# Disco-Cart_2.net
KiCad netlist of a schematic drawn in EAGLE
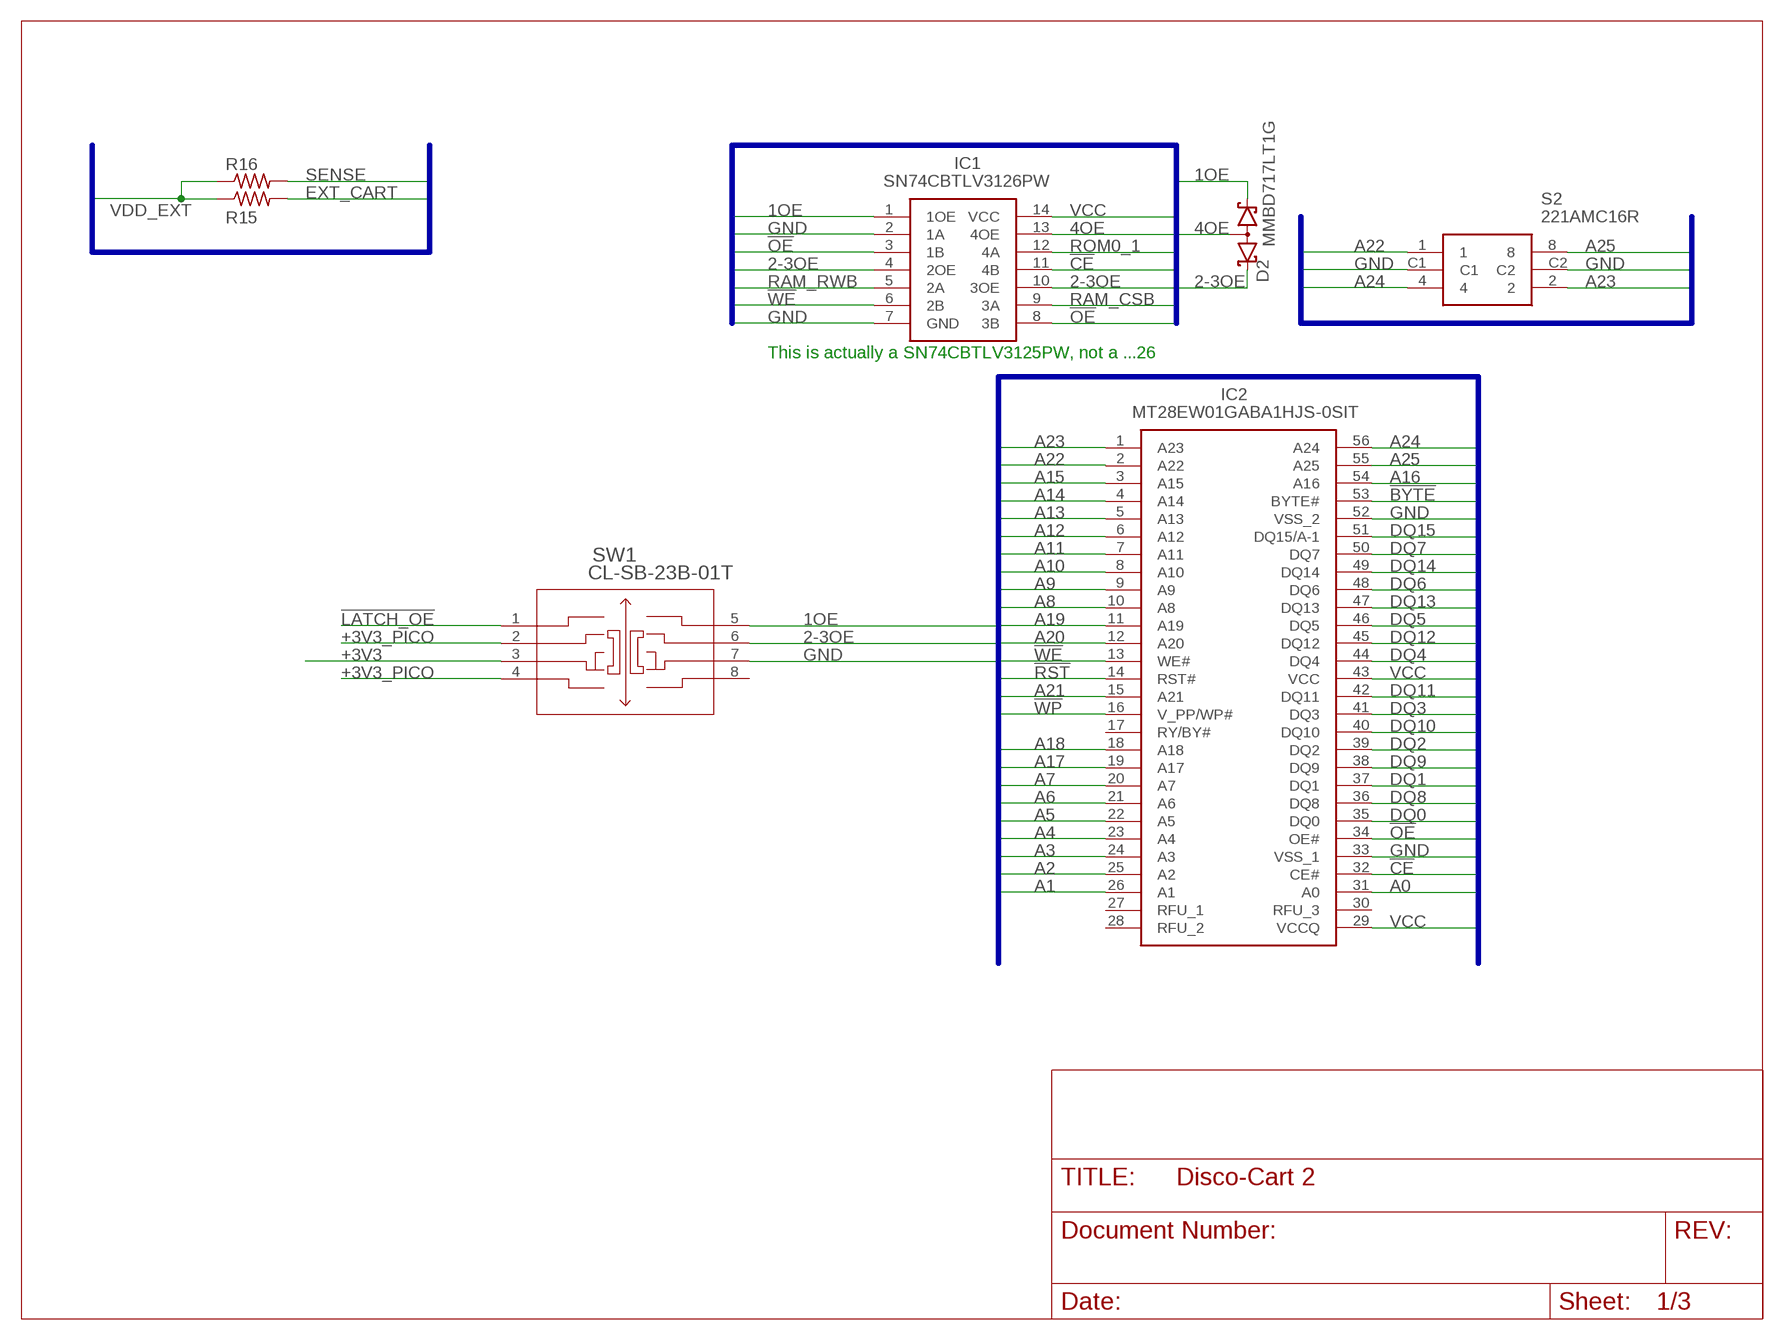
[diagram p0: schematic, sheet 1]
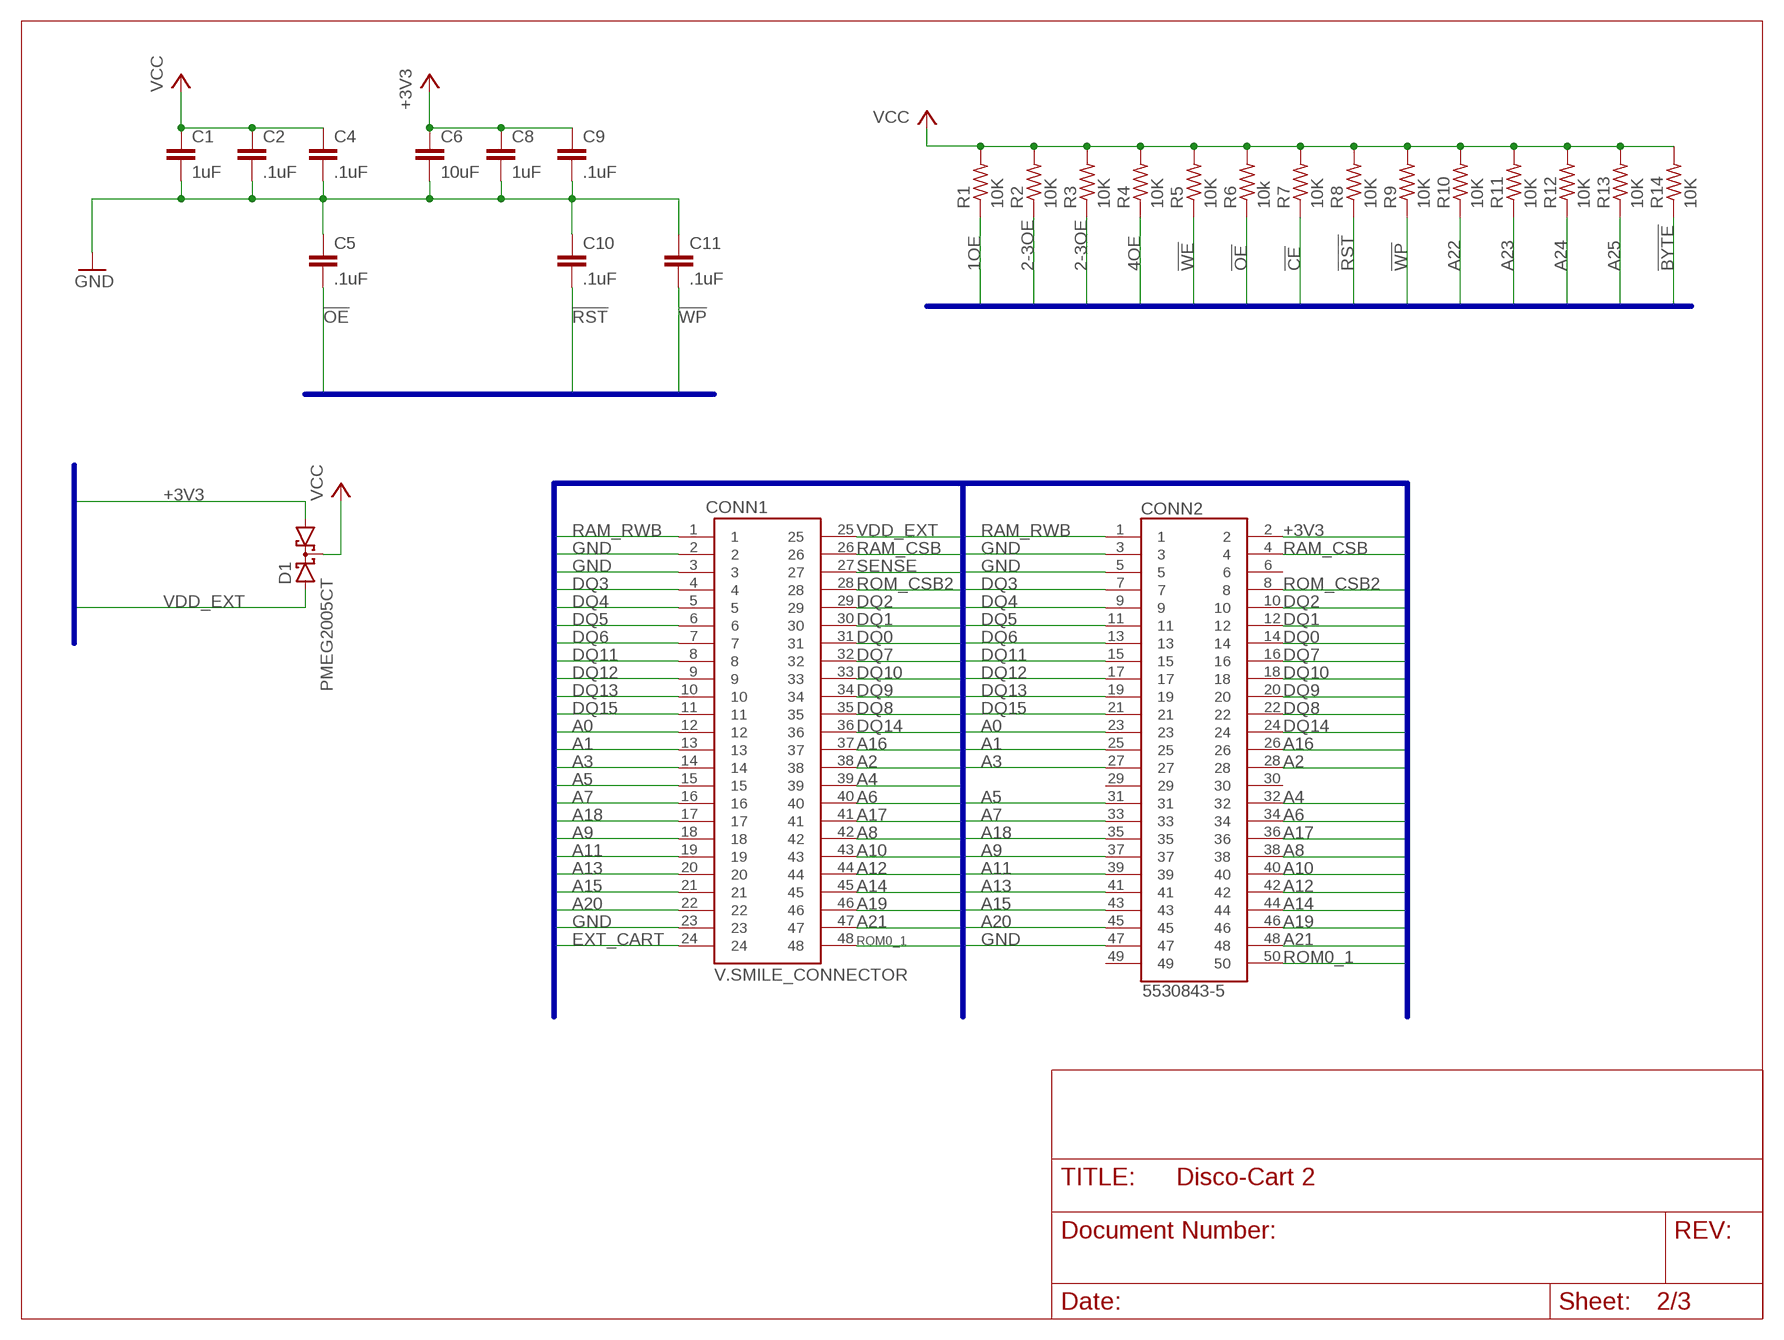
[diagram p1: schematic, sheet 2]
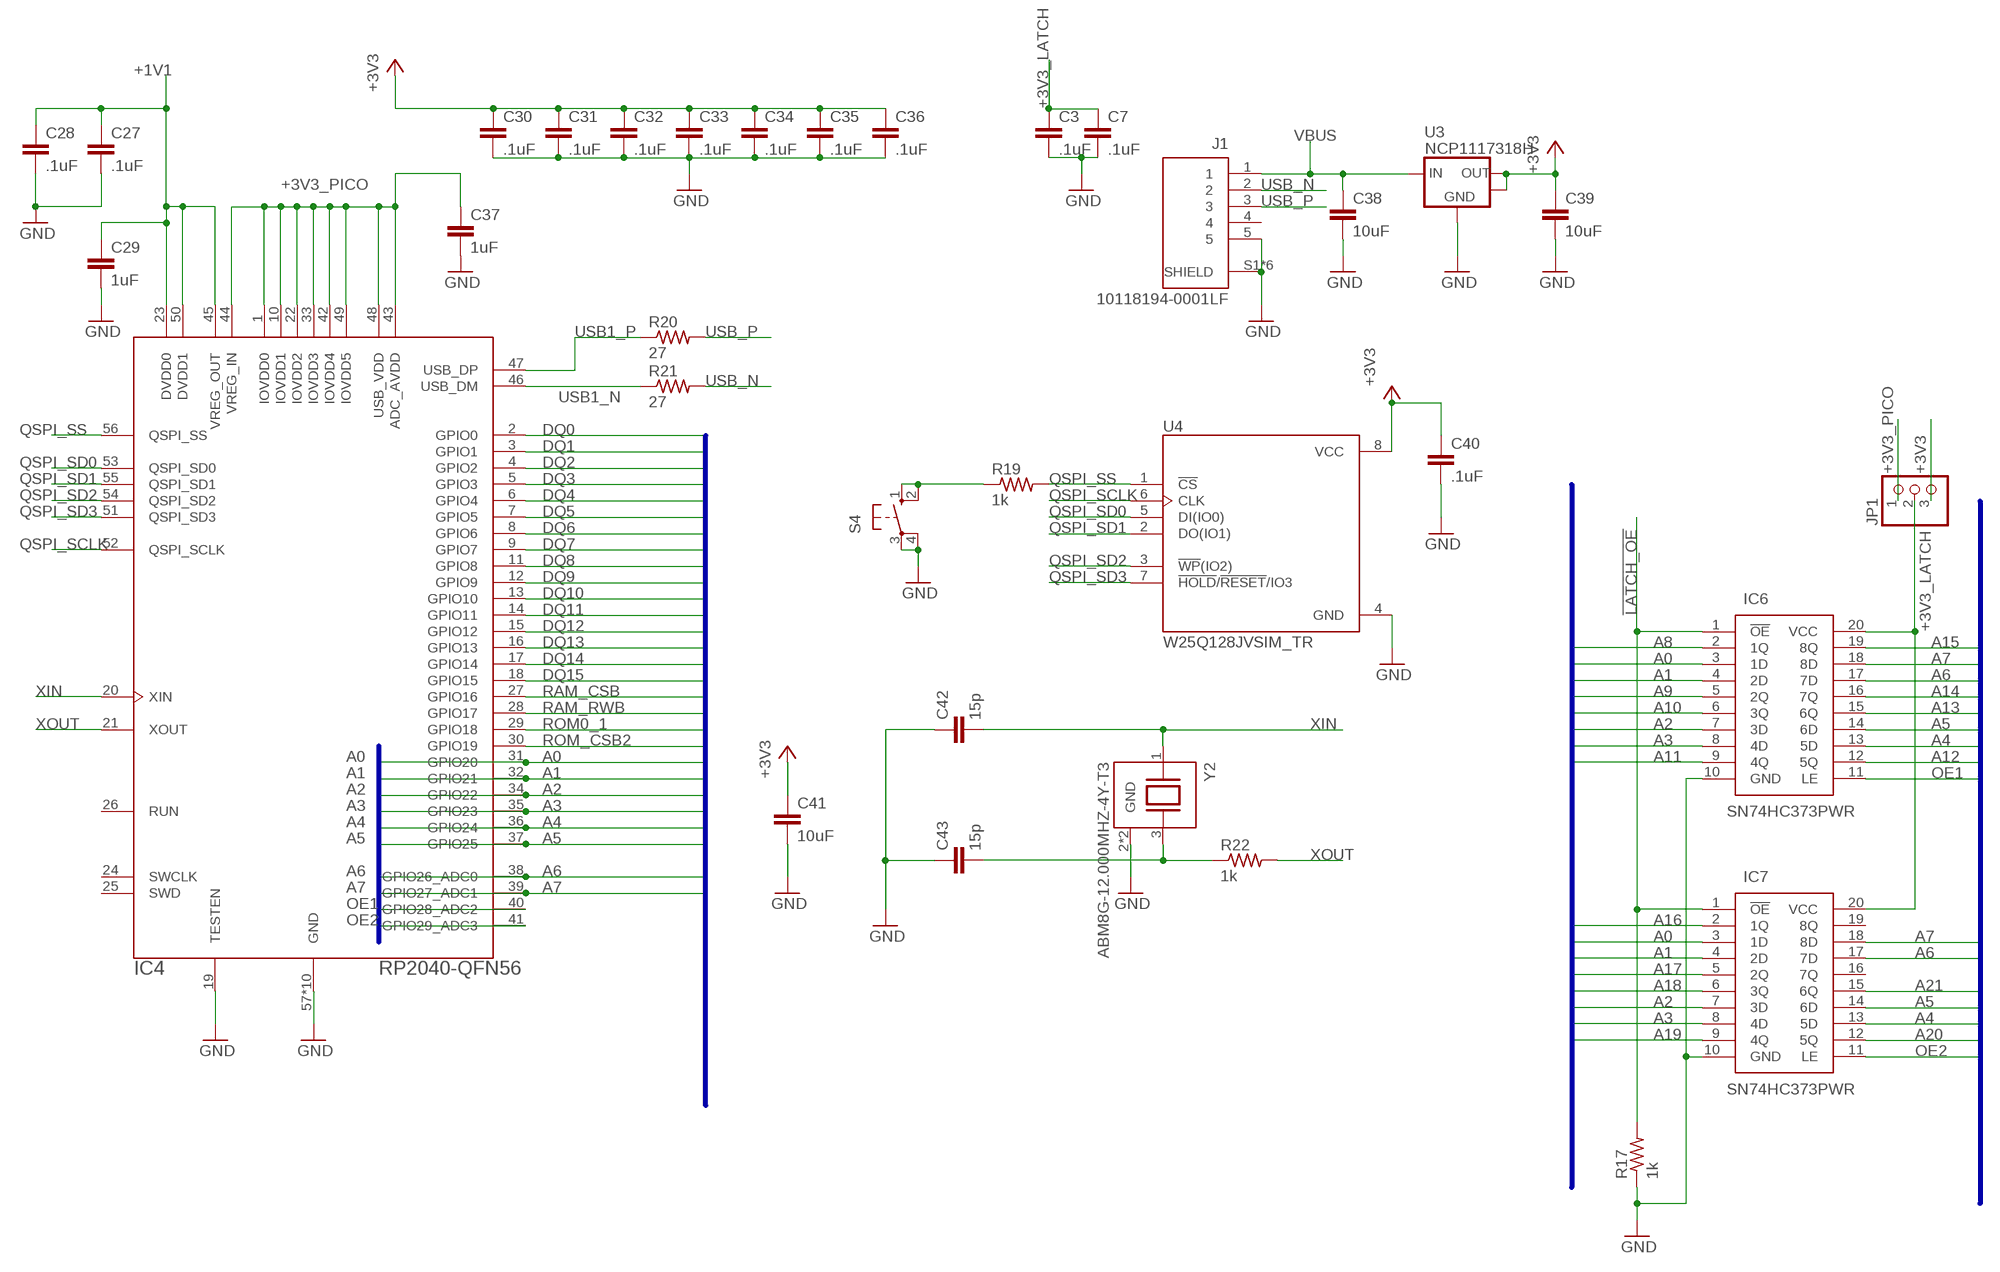
[diagram p2: schematic, sheet 3]

(export (version "E")
  (design (tool "Eeschema 10.0.6"))
  (components
    (comp (ref "C1")
      (value "1uF")
      (footprint "eagle-import:C0805")
      (libsource (lib "eagle-import") (part "C-EUC0805"))
    )
    (comp (ref "C2")
      (value ".1uF")
      (footprint "eagle-import:C0805")
      (libsource (lib "eagle-import") (part "C-EUC0805"))
    )
    (comp (ref "C4")
      (value ".1uF")
      (footprint "eagle-import:C0805")
      (libsource (lib "eagle-import") (part "C-EUC0805"))
    )
    (comp (ref "C5")
      (value ".1uF")
      (footprint "eagle-import:C0805")
      (libsource (lib "eagle-import") (part "C-EUC0805"))
    )
    (comp (ref "C6")
      (value "10uF")
      (footprint "eagle-import:C0805")
      (libsource (lib "eagle-import") (part "C-EUC0805"))
    )
    (comp (ref "C8")
      (value "1uF")
      (footprint "eagle-import:C0805")
      (libsource (lib "eagle-import") (part "C-EUC0805"))
    )
    (comp (ref "C9")
      (value ".1uF")
      (footprint "eagle-import:C0805")
      (libsource (lib "eagle-import") (part "C-EUC0805"))
    )
    (comp (ref "C10")
      (value ".1uF")
      (footprint "eagle-import:C0805")
      (libsource (lib "eagle-import") (part "C-EUC0805"))
    )
    (comp (ref "C11")
      (value ".1uF")
      (footprint "eagle-import:C0805")
      (libsource (lib "eagle-import") (part "C-EUC0805"))
    )
    (comp (ref "CONN1")
      (value "V.SMILE_CONNECTOR")
      (footprint "eagle-import:V.SMILE_CONNECTOR")
      (libsource (lib "eagle-import") (part "V.SMILE_CONNECTOR"))
    )
    (comp (ref "CONN2")
      (value "5530843-5")
      (footprint "eagle-import:TE_5530843-5")
      (fields (field (name "MANUFACTURER") "TE Connectivity"))
      (libsource (lib "eagle-import") (part "5530843-5"))
    )
    (comp (ref "D1")
      (value "PMEG2005CT")
      (footprint "eagle-import:SOT23")
      (libsource (lib "eagle-import") (part "BAS40-05"))
    )
    (comp (ref "R1")
      (value "10K")
      (footprint "eagle-import:M0805")
      (libsource (lib "eagle-import") (part "R-US_M0805"))
    )
    (comp (ref "R2")
      (value "10K")
      (footprint "eagle-import:M0805")
      (libsource (lib "eagle-import") (part "R-US_M0805"))
    )
    (comp (ref "R3")
      (value "10K")
      (footprint "eagle-import:M0805")
      (libsource (lib "eagle-import") (part "R-US_M0805"))
    )
    (comp (ref "R4")
      (value "10K")
      (footprint "eagle-import:M0805")
      (libsource (lib "eagle-import") (part "R-US_M0805"))
    )
    (comp (ref "R5")
      (value "10K")
      (footprint "eagle-import:M0805")
      (libsource (lib "eagle-import") (part "R-US_M0805"))
    )
    (comp (ref "R6")
      (value "10k")
      (footprint "eagle-import:M0805")
      (libsource (lib "eagle-import") (part "R-US_M0805"))
    )
    (comp (ref "R7")
      (value "10K")
      (footprint "eagle-import:M0805")
      (libsource (lib "eagle-import") (part "R-US_M0805"))
    )
    (comp (ref "R8")
      (value "10K")
      (footprint "eagle-import:M0805")
      (libsource (lib "eagle-import") (part "R-US_M0805"))
    )
    (comp (ref "R9")
      (value "10K")
      (footprint "eagle-import:M0805")
      (libsource (lib "eagle-import") (part "R-US_M0805"))
    )
    (comp (ref "R10")
      (value "10K")
      (footprint "eagle-import:M0805")
      (libsource (lib "eagle-import") (part "R-US_M0805"))
    )
    (comp (ref "R11")
      (value "10K")
      (footprint "eagle-import:M0805")
      (libsource (lib "eagle-import") (part "R-US_M0805"))
    )
    (comp (ref "R12")
      (value "10K")
      (footprint "eagle-import:M0805")
      (libsource (lib "eagle-import") (part "R-US_M0805"))
    )
    (comp (ref "R13")
      (value "10K")
      (footprint "eagle-import:M0805")
      (libsource (lib "eagle-import") (part "R-US_M0805"))
    )
    (comp (ref "R14")
      (value "10K")
      (footprint "eagle-import:M0805")
      (libsource (lib "eagle-import") (part "R-US_M0805"))
    )
    (comp (ref "D2")
      (value "MMBD717LT1G")
      (footprint "eagle-import:SOT65P220X100-3N")
      (fields (field (name "MOUSER_PART_NUMBER") "863-MMBD717LT1G"))
      (libsource (lib "eagle-import") (part "MMBD717LT1G"))
    )
    (comp (ref "IC1")
      (value "SN74CBTLV3126PW")
      (footprint "eagle-import:SOP65P640X120-14N")
      (fields (field (name "MOUSER_PART_NUMBER") "595-SN74CBTLV3126PW"))
      (libsource (lib "eagle-import") (part "SN74CBTLV3126PW"))
    )
    (comp (ref "IC2")
      (value "MT28EW01GABA1HJS-0SIT")
      (footprint "eagle-import:SOP50P2000X120-56N")
      (fields (field (name "MOUSER_PART_NUMBER") "340-278002-TRAY"))
      (libsource (lib "eagle-import") (part "MT28EW01GABA1HJS-0SIT"))
    )
    (comp (ref "R15")
      (value "R-US_R0603")
      (footprint "eagle-import:R0603")
      (libsource (lib "eagle-import") (part "R-US_R0603"))
    )
    (comp (ref "R16")
      (value "R-US_R0603")
      (footprint "eagle-import:R0603")
      (libsource (lib "eagle-import") (part "R-US_R0603"))
    )
    (comp (ref "S2")
      (value "221AMC16R")
      (footprint "eagle-import:221AMC16R")
      (fields (field (name "MOUSER_PART_NUMBER") "774-221AMC16R"))
      (libsource (lib "eagle-import") (part "221AMC16R"))
    )
    (comp (ref "SW1")
      (value "CL-SB-23B-01T")
      (footprint "eagle-import:CL-SB-23B_NDC")
      (fields (field (name "COPYRIGHT") "Copyright (C) 2024 Ultra Librarian. All rights reserved."))
      (libsource (lib "eagle-import") (part "CL-SB-23B-01T"))
    )
    (comp (ref "C3")
      (value ".1uF")
      (footprint "eagle-import:C0402")
      (libsource (lib "eagle-import") (part "C-EUC0402"))
    )
    (comp (ref "C7")
      (value ".1uF")
      (footprint "eagle-import:C0402")
      (libsource (lib "eagle-import") (part "C-EUC0402"))
    )
    (comp (ref "C27")
      (value ".1uF")
      (footprint "eagle-import:C0402")
      (libsource (lib "eagle-import") (part "C-EUC0402"))
    )
    (comp (ref "C28")
      (value ".1uF")
      (footprint "eagle-import:C0402")
      (libsource (lib "eagle-import") (part "C-EUC0402"))
    )
    (comp (ref "C29")
      (value "1uF")
      (footprint "eagle-import:C0402")
      (libsource (lib "eagle-import") (part "C-EUC0402"))
    )
    (comp (ref "C30")
      (value ".1uF")
      (footprint "eagle-import:C0402")
      (libsource (lib "eagle-import") (part "C-EUC0402"))
    )
    (comp (ref "C31")
      (value ".1uF")
      (footprint "eagle-import:C0402")
      (libsource (lib "eagle-import") (part "C-EUC0402"))
    )
    (comp (ref "C32")
      (value ".1uF")
      (footprint "eagle-import:C0402")
      (libsource (lib "eagle-import") (part "C-EUC0402"))
    )
    (comp (ref "C33")
      (value ".1uF")
      (footprint "eagle-import:C0402")
      (libsource (lib "eagle-import") (part "C-EUC0402"))
    )
    (comp (ref "C34")
      (value ".1uF")
      (footprint "eagle-import:C0402")
      (libsource (lib "eagle-import") (part "C-EUC0402"))
    )
    (comp (ref "C35")
      (value ".1uF")
      (footprint "eagle-import:C0402")
      (libsource (lib "eagle-import") (part "C-EUC0402"))
    )
    (comp (ref "C36")
      (value ".1uF")
      (footprint "eagle-import:C0402")
      (libsource (lib "eagle-import") (part "C-EUC0402"))
    )
    (comp (ref "C37")
      (value "1uF")
      (footprint "eagle-import:C0402")
      (libsource (lib "eagle-import") (part "C-EUC0402"))
    )
    (comp (ref "C38")
      (value "10uF")
      (footprint "eagle-import:C0805")
      (libsource (lib "eagle-import") (part "C-EUC0805"))
    )
    (comp (ref "C39")
      (value "10uF")
      (footprint "eagle-import:C0805")
      (libsource (lib "eagle-import") (part "C-EUC0805"))
    )
    (comp (ref "C40")
      (value ".1uF")
      (footprint "eagle-import:C0402")
      (libsource (lib "eagle-import") (part "C-EUC0402"))
    )
    (comp (ref "C41")
      (value "10uF")
      (footprint "eagle-import:C0805")
      (libsource (lib "eagle-import") (part "C-EUC0805"))
    )
    (comp (ref "C42")
      (value "15p")
      (footprint "eagle-import:C0402")
      (libsource (lib "eagle-import") (part "C-EUC0402"))
    )
    (comp (ref "C43")
      (value "15p")
      (footprint "eagle-import:C0402")
      (libsource (lib "eagle-import") (part "C-EUC0402"))
    )
    (comp (ref "IC4")
      (value "RP2040-QFN56")
      (footprint "eagle-import:RP2040-QFN-56")
      (libsource (lib "eagle-import") (part "RP2040-QFN56"))
    )
    (comp (ref "IC6")
      (value "SN74HC373PWR")
      (footprint "eagle-import:SOP65P640X120-20N")
      (fields (field (name "MOUSER_PART_NUMBER") "595-SN74HC373PWR"))
      (libsource (lib "eagle-import") (part "SN74HC373PWR"))
    )
    (comp (ref "IC7")
      (value "SN74HC373PWR")
      (footprint "eagle-import:SOP65P640X120-20N")
      (fields (field (name "MOUSER_PART_NUMBER") "595-SN74HC373PWR"))
      (libsource (lib "eagle-import") (part "SN74HC373PWR"))
    )
    (comp (ref "J1")
      (value "10118194-0001LF")
      (footprint "eagle-import:AMPHENOL_10118194-0001LF")
      (fields (field (name "MANUFACTURER") "Amphenol ICC"))
      (libsource (lib "eagle-import") (part "10118194-0001LF"))
    )
    (comp (ref "JP1")
      (value "PINHD-1X3")
      (footprint "eagle-import:1X03")
      (libsource (lib "eagle-import") (part "PINHD-1X3"))
    )
    (comp (ref "R17")
      (value "1k")
      (footprint "eagle-import:R0805")
      (libsource (lib "eagle-import") (part "R-US_R0805"))
    )
    (comp (ref "R19")
      (value "1k")
      (footprint "eagle-import:R0402")
      (libsource (lib "eagle-import") (part "R-US_R0402"))
    )
    (comp (ref "R20")
      (value "27")
      (footprint "eagle-import:R0402")
      (libsource (lib "eagle-import") (part "R-US_R0402"))
    )
    (comp (ref "R21")
      (value "27")
      (footprint "eagle-import:R0402")
      (libsource (lib "eagle-import") (part "R-US_R0402"))
    )
    (comp (ref "R22")
      (value "1k")
      (footprint "eagle-import:R0402")
      (libsource (lib "eagle-import") (part "R-US_R0402"))
    )
    (comp (ref "S4")
      (value "10-XX")
      (footprint "eagle-import:B3F-10XX")
      (fields (field (name "MPN") "B3F-1000"))
      (libsource (lib "eagle-import") (part "10-XX"))
    )
    (comp (ref "U3")
      (value "NCP1117318H")
      (footprint "eagle-import:SOT223")
      (fields (field (name "MF") "ON Semiconductor") (field (name "MP") "NCP1117"))
      (libsource (lib "eagle-import") (part "NCP1117318H"))
    )
    (comp (ref "U4")
      (value "W25Q128JVSIM_TR")
      (footprint "eagle-import:SOIC127P790X216-8N")
      (fields
        (field (name "DIGIKEY_PART_NUMBER") "W25Q128JVSIMTR-ND")
        (field (name "MF") "Winbond Electronics")
        (field (name "MP") "W25Q128JVSIM TR")
      )
      (libsource (lib "eagle-import") (part "W25Q128JVSIM_TR"))
    )
    (comp (ref "Y2")
      (value "ABM8G-12.000MHZ-4Y-T3")
      (footprint "eagle-import:XTAL_ABM8G-12.000MHZ-4Y-T3")
      (fields (field (name "MANUFACTURER") "Abracon"))
      (libsource (lib "eagle-import") (part "ABM8G-12.000MHZ-4Y-T3"))
    )
  )
  (nets
    (net (code "17") (name "+1V1") (class "Default")
      (node (ref "C27") (pin "1") (pinfunction "1_1") (pintype "passive"))
      (node (ref "C28") (pin "1") (pinfunction "1_1") (pintype "passive"))
      (node (ref "C29") (pin "1") (pinfunction "1_1") (pintype "passive"))
      (node (ref "IC4") (pin "23") (pinfunction "DVDD0_23") (pintype "power_in"))
      (node (ref "IC4") (pin "45") (pinfunction "VREG_OUT_45") (pintype "power_in"))
      (node (ref "IC4") (pin "50") (pinfunction "DVDD1_50") (pintype "power_in"))
    )
    (net (code "18") (name "+3V3") (class "Default")
      (node (ref "C30") (pin "1") (pinfunction "1_1") (pintype "passive"))
      (node (ref "C31") (pin "1") (pinfunction "1_1") (pintype "passive"))
      (node (ref "C32") (pin "1") (pinfunction "1_1") (pintype "passive"))
      (node (ref "C33") (pin "1") (pinfunction "1_1") (pintype "passive"))
      (node (ref "C34") (pin "1") (pinfunction "1_1") (pintype "passive"))
      (node (ref "C35") (pin "1") (pinfunction "1_1") (pintype "passive"))
      (node (ref "C36") (pin "1") (pinfunction "1_1") (pintype "passive"))
      (node (ref "C39") (pin "1") (pinfunction "1_1") (pintype "passive"))
      (node (ref "C40") (pin "1") (pinfunction "1_1") (pintype "passive"))
      (node (ref "C41") (pin "1") (pinfunction "1_1") (pintype "passive"))
      (node (ref "C6") (pin "1") (pinfunction "1_1") (pintype "passive"))
      (node (ref "C8") (pin "1") (pinfunction "1_1") (pintype "passive"))
      (node (ref "C9") (pin "1") (pinfunction "1_1") (pintype "passive"))
      (node (ref "CONN2") (pin "2") (pinfunction "2_2") (pintype "passive"))
      (node (ref "D1") (pin "1") (pinfunction "A1_1") (pintype "passive"))
      (node (ref "JP1") (pin "3") (pinfunction "3_3") (pintype "passive"))
      (node (ref "SW1") (pin "3") (pinfunction "3_3") (pintype "passive"))
      (node (ref "U3") (pin "2") (pinfunction "OUT_2") (pintype "passive"))
      (node (ref "U3") (pin "TAB") (pinfunction "OUT_TAB") (pintype "passive"))
      (node (ref "U4") (pin "8") (pinfunction "VCC_8") (pintype "power_in"))
    )
    (net (code "19") (name "+3V3_LATCH") (class "Default")
      (node (ref "C3") (pin "1") (pinfunction "1_1") (pintype "passive"))
      (node (ref "C7") (pin "1") (pinfunction "1_1") (pintype "passive"))
      (node (ref "IC6") (pin "20") (pinfunction "VCC_20") (pintype "bidirectional"))
      (node (ref "IC7") (pin "20") (pinfunction "VCC_20") (pintype "bidirectional"))
      (node (ref "JP1") (pin "2") (pinfunction "2_2") (pintype "passive"))
    )
    (net (code "20") (name "+3V3_PICO") (class "Default")
      (node (ref "C37") (pin "1") (pinfunction "1_1") (pintype "passive"))
      (node (ref "IC4") (pin "1") (pinfunction "IOVDD0_1") (pintype "power_in"))
      (node (ref "IC4") (pin "10") (pinfunction "IOVDD1_10") (pintype "power_in"))
      (node (ref "IC4") (pin "22") (pinfunction "IOVDD2_22") (pintype "power_in"))
      (node (ref "IC4") (pin "33") (pinfunction "IOVDD3_33") (pintype "power_in"))
      (node (ref "IC4") (pin "42") (pinfunction "IOVDD4_42") (pintype "power_in"))
      (node (ref "IC4") (pin "43") (pinfunction "ADC_AVDD_43") (pintype "power_in"))
      (node (ref "IC4") (pin "44") (pinfunction "VREG_IN_44") (pintype "power_in"))
      (node (ref "IC4") (pin "48") (pinfunction "USB_VDD_48") (pintype "power_in"))
      (node (ref "IC4") (pin "49") (pinfunction "IOVDD5_49") (pintype "power_in"))
      (node (ref "JP1") (pin "1") (pinfunction "1_1") (pintype "passive"))
      (node (ref "SW1") (pin "2") (pinfunction "2_2") (pintype "passive"))
      (node (ref "SW1") (pin "4") (pinfunction "4_4") (pintype "passive"))
    )
    (net (code "25") (name "1OE") (class "Default")
      (node (ref "D2") (pin "1") (pinfunction "K2_1") (pintype "passive"))
      (node (ref "IC1") (pin "1") (pinfunction "1OE_1") (pintype "bidirectional"))
      (node (ref "R1") (pin "1") (pinfunction "1_1") (pintype "passive"))
      (node (ref "SW1") (pin "5") (pinfunction "8_5") (pintype "passive"))
    )
    (net (code "26") (name "2-3OE") (class "Default")
      (node (ref "D2") (pin "2") (pinfunction "K1_2") (pintype "passive"))
      (node (ref "IC1") (pin "10") (pinfunction "3OE_10") (pintype "bidirectional"))
      (node (ref "IC1") (pin "4") (pinfunction "2OE_4") (pintype "bidirectional"))
      (node (ref "R2") (pin "1") (pinfunction "1_1") (pintype "passive"))
      (node (ref "R3") (pin "1") (pinfunction "1_1") (pintype "passive"))
      (node (ref "SW1") (pin "6") (pinfunction "7_6") (pintype "passive"))
    )
    (net (code "27") (name "4OE") (class "Default")
      (node (ref "D2") (pin "3") (pinfunction "AA_3") (pintype "passive"))
      (node (ref "IC1") (pin "13") (pinfunction "4OE_13") (pintype "bidirectional"))
      (node (ref "R4") (pin "1") (pinfunction "1_1") (pintype "passive"))
    )
    (net (code "28") (name "A0") (class "Default")
      (node (ref "CONN1") (pin "12") (pinfunction "12_12") (pintype "bidirectional"))
      (node (ref "CONN2") (pin "23") (pinfunction "23_23") (pintype "passive"))
      (node (ref "IC2") (pin "31") (pinfunction "A0_31") (pintype "bidirectional"))
      (node (ref "IC4") (pin "31") (pinfunction "GPIO20_31") (pintype "bidirectional"))
      (node (ref "IC6") (pin "3") (pinfunction "1D_3") (pintype "bidirectional"))
      (node (ref "IC7") (pin "3") (pinfunction "1D_3") (pintype "bidirectional"))
    )
    (net (code "29") (name "A1") (class "Default")
      (node (ref "CONN1") (pin "13") (pinfunction "13_13") (pintype "bidirectional"))
      (node (ref "CONN2") (pin "25") (pinfunction "25_25") (pintype "passive"))
      (node (ref "IC2") (pin "26") (pinfunction "A1_26") (pintype "bidirectional"))
      (node (ref "IC4") (pin "32") (pinfunction "GPIO21_32") (pintype "bidirectional"))
      (node (ref "IC6") (pin "4") (pinfunction "2D_4") (pintype "bidirectional"))
      (node (ref "IC7") (pin "4") (pinfunction "2D_4") (pintype "bidirectional"))
    )
    (net (code "30") (name "A2") (class "Default")
      (node (ref "CONN1") (pin "38") (pinfunction "38_38") (pintype "bidirectional"))
      (node (ref "CONN2") (pin "28") (pinfunction "28_28") (pintype "passive"))
      (node (ref "IC2") (pin "25") (pinfunction "A2_25") (pintype "bidirectional"))
      (node (ref "IC4") (pin "34") (pinfunction "GPIO22_34") (pintype "bidirectional"))
      (node (ref "IC6") (pin "7") (pinfunction "3D_7") (pintype "bidirectional"))
      (node (ref "IC7") (pin "7") (pinfunction "3D_7") (pintype "bidirectional"))
    )
    (net (code "31") (name "A3") (class "Default")
      (node (ref "CONN1") (pin "14") (pinfunction "14_14") (pintype "bidirectional"))
      (node (ref "CONN2") (pin "27") (pinfunction "27_27") (pintype "passive"))
      (node (ref "IC2") (pin "24") (pinfunction "A3_24") (pintype "bidirectional"))
      (node (ref "IC4") (pin "35") (pinfunction "GPIO23_35") (pintype "bidirectional"))
      (node (ref "IC6") (pin "8") (pinfunction "4D_8") (pintype "bidirectional"))
      (node (ref "IC7") (pin "8") (pinfunction "4D_8") (pintype "bidirectional"))
    )
    (net (code "32") (name "A4") (class "Default")
      (node (ref "CONN1") (pin "39") (pinfunction "39_39") (pintype "bidirectional"))
      (node (ref "CONN2") (pin "32") (pinfunction "32_32") (pintype "passive"))
      (node (ref "IC2") (pin "23") (pinfunction "A4_23") (pintype "bidirectional"))
      (node (ref "IC4") (pin "36") (pinfunction "GPIO24_36") (pintype "bidirectional"))
      (node (ref "IC6") (pin "13") (pinfunction "5D_13") (pintype "bidirectional"))
      (node (ref "IC7") (pin "13") (pinfunction "5D_13") (pintype "bidirectional"))
    )
    (net (code "33") (name "A5") (class "Default")
      (node (ref "CONN1") (pin "15") (pinfunction "15_15") (pintype "bidirectional"))
      (node (ref "CONN2") (pin "31") (pinfunction "31_31") (pintype "passive"))
      (node (ref "IC2") (pin "22") (pinfunction "A5_22") (pintype "bidirectional"))
      (node (ref "IC4") (pin "37") (pinfunction "GPIO25_37") (pintype "bidirectional"))
      (node (ref "IC6") (pin "14") (pinfunction "6D_14") (pintype "bidirectional"))
      (node (ref "IC7") (pin "14") (pinfunction "6D_14") (pintype "bidirectional"))
    )
    (net (code "34") (name "A6") (class "Default")
      (node (ref "CONN1") (pin "40") (pinfunction "40_40") (pintype "bidirectional"))
      (node (ref "CONN2") (pin "34") (pinfunction "34_34") (pintype "passive"))
      (node (ref "IC2") (pin "21") (pinfunction "A6_21") (pintype "bidirectional"))
      (node (ref "IC4") (pin "38") (pinfunction "GPIO26_ADC0_38") (pintype "bidirectional"))
      (node (ref "IC6") (pin "17") (pinfunction "7D_17") (pintype "bidirectional"))
      (node (ref "IC7") (pin "17") (pinfunction "7D_17") (pintype "bidirectional"))
    )
    (net (code "35") (name "A7") (class "Default")
      (node (ref "CONN1") (pin "16") (pinfunction "16_16") (pintype "bidirectional"))
      (node (ref "CONN2") (pin "33") (pinfunction "33_33") (pintype "passive"))
      (node (ref "IC2") (pin "20") (pinfunction "A7_20") (pintype "bidirectional"))
      (node (ref "IC4") (pin "39") (pinfunction "GPIO27_ADC1_39") (pintype "bidirectional"))
      (node (ref "IC6") (pin "18") (pinfunction "8D_18") (pintype "bidirectional"))
      (node (ref "IC7") (pin "18") (pinfunction "8D_18") (pintype "bidirectional"))
    )
    (net (code "36") (name "A8") (class "Default")
      (node (ref "CONN1") (pin "42") (pinfunction "42_42") (pintype "bidirectional"))
      (node (ref "CONN2") (pin "38") (pinfunction "38_38") (pintype "passive"))
      (node (ref "IC2") (pin "10") (pinfunction "A8_10") (pintype "bidirectional"))
      (node (ref "IC6") (pin "2") (pinfunction "1Q_2") (pintype "bidirectional"))
    )
    (net (code "37") (name "A9") (class "Default")
      (node (ref "CONN1") (pin "18") (pinfunction "18_18") (pintype "bidirectional"))
      (node (ref "CONN2") (pin "37") (pinfunction "37_37") (pintype "passive"))
      (node (ref "IC2") (pin "9") (pinfunction "A9_9") (pintype "bidirectional"))
      (node (ref "IC6") (pin "5") (pinfunction "2Q_5") (pintype "bidirectional"))
    )
    (net (code "38") (name "A10") (class "Default")
      (node (ref "CONN1") (pin "43") (pinfunction "43_43") (pintype "bidirectional"))
      (node (ref "CONN2") (pin "40") (pinfunction "40_40") (pintype "passive"))
      (node (ref "IC2") (pin "8") (pinfunction "A10_8") (pintype "bidirectional"))
      (node (ref "IC6") (pin "6") (pinfunction "3Q_6") (pintype "bidirectional"))
    )
    (net (code "39") (name "A11") (class "Default")
      (node (ref "CONN1") (pin "19") (pinfunction "19_19") (pintype "bidirectional"))
      (node (ref "CONN2") (pin "39") (pinfunction "39_39") (pintype "passive"))
      (node (ref "IC2") (pin "7") (pinfunction "A11_7") (pintype "bidirectional"))
      (node (ref "IC6") (pin "9") (pinfunction "4Q_9") (pintype "bidirectional"))
    )
    (net (code "40") (name "A12") (class "Default")
      (node (ref "CONN1") (pin "44") (pinfunction "44_44") (pintype "bidirectional"))
      (node (ref "CONN2") (pin "42") (pinfunction "42_42") (pintype "passive"))
      (node (ref "IC2") (pin "6") (pinfunction "A12_6") (pintype "bidirectional"))
      (node (ref "IC6") (pin "12") (pinfunction "5Q_12") (pintype "bidirectional"))
    )
    (net (code "41") (name "A13") (class "Default")
      (node (ref "CONN1") (pin "20") (pinfunction "20_20") (pintype "bidirectional"))
      (node (ref "CONN2") (pin "41") (pinfunction "41_41") (pintype "passive"))
      (node (ref "IC2") (pin "5") (pinfunction "A13_5") (pintype "bidirectional"))
      (node (ref "IC6") (pin "15") (pinfunction "6Q_15") (pintype "bidirectional"))
    )
    (net (code "42") (name "A14") (class "Default")
      (node (ref "CONN1") (pin "45") (pinfunction "45_45") (pintype "bidirectional"))
      (node (ref "CONN2") (pin "44") (pinfunction "44_44") (pintype "passive"))
      (node (ref "IC2") (pin "4") (pinfunction "A14_4") (pintype "bidirectional"))
      (node (ref "IC6") (pin "16") (pinfunction "7Q_16") (pintype "bidirectional"))
    )
    (net (code "43") (name "A15") (class "Default")
      (node (ref "CONN1") (pin "21") (pinfunction "21_21") (pintype "bidirectional"))
      (node (ref "CONN2") (pin "43") (pinfunction "43_43") (pintype "passive"))
      (node (ref "IC2") (pin "3") (pinfunction "A15_3") (pintype "bidirectional"))
      (node (ref "IC6") (pin "19") (pinfunction "8Q_19") (pintype "bidirectional"))
    )
    (net (code "44") (name "A16") (class "Default")
      (node (ref "CONN1") (pin "37") (pinfunction "37_37") (pintype "bidirectional"))
      (node (ref "CONN2") (pin "26") (pinfunction "26_26") (pintype "passive"))
      (node (ref "IC2") (pin "54") (pinfunction "A16_54") (pintype "bidirectional"))
      (node (ref "IC7") (pin "2") (pinfunction "1Q_2") (pintype "bidirectional"))
    )
    (net (code "45") (name "A17") (class "Default")
      (node (ref "CONN1") (pin "41") (pinfunction "41_41") (pintype "bidirectional"))
      (node (ref "CONN2") (pin "36") (pinfunction "36_36") (pintype "passive"))
      (node (ref "IC2") (pin "19") (pinfunction "A17_19") (pintype "bidirectional"))
      (node (ref "IC7") (pin "5") (pinfunction "2Q_5") (pintype "bidirectional"))
    )
    (net (code "46") (name "A18") (class "Default")
      (node (ref "CONN1") (pin "17") (pinfunction "17_17") (pintype "bidirectional"))
      (node (ref "CONN2") (pin "35") (pinfunction "35_35") (pintype "passive"))
      (node (ref "IC2") (pin "18") (pinfunction "A18_18") (pintype "bidirectional"))
      (node (ref "IC7") (pin "6") (pinfunction "3Q_6") (pintype "bidirectional"))
    )
    (net (code "47") (name "A19") (class "Default")
      (node (ref "CONN1") (pin "46") (pinfunction "46_46") (pintype "bidirectional"))
      (node (ref "CONN2") (pin "46") (pinfunction "46_46") (pintype "passive"))
      (node (ref "IC2") (pin "11") (pinfunction "A19_11") (pintype "bidirectional"))
      (node (ref "IC7") (pin "9") (pinfunction "4Q_9") (pintype "bidirectional"))
    )
    (net (code "48") (name "A20") (class "Default")
      (node (ref "CONN1") (pin "22") (pinfunction "22_22") (pintype "bidirectional"))
      (node (ref "CONN2") (pin "45") (pinfunction "45_45") (pintype "passive"))
      (node (ref "IC2") (pin "12") (pinfunction "A20_12") (pintype "bidirectional"))
      (node (ref "IC7") (pin "12") (pinfunction "5Q_12") (pintype "bidirectional"))
    )
    (net (code "49") (name "A21") (class "Default")
      (node (ref "CONN1") (pin "47") (pinfunction "47_47") (pintype "bidirectional"))
      (node (ref "CONN2") (pin "48") (pinfunction "48_48") (pintype "passive"))
      (node (ref "IC2") (pin "15") (pinfunction "A21_15") (pintype "bidirectional"))
      (node (ref "IC7") (pin "15") (pinfunction "6Q_15") (pintype "bidirectional"))
    )
    (net (code "50") (name "A22") (class "Default")
      (node (ref "IC2") (pin "2") (pinfunction "A22_2") (pintype "bidirectional"))
      (node (ref "R10") (pin "1") (pinfunction "1_1") (pintype "passive"))
      (node (ref "S2") (pin "1") (pinfunction "1_1") (pintype "bidirectional"))
    )
    (net (code "51") (name "A23") (class "Default")
      (node (ref "IC2") (pin "1") (pinfunction "A23_1") (pintype "bidirectional"))
      (node (ref "R11") (pin "1") (pinfunction "1_1") (pintype "passive"))
      (node (ref "S2") (pin "2") (pinfunction "2_2") (pintype "bidirectional"))
    )
    (net (code "52") (name "A24") (class "Default")
      (node (ref "IC2") (pin "56") (pinfunction "A24_56") (pintype "bidirectional"))
      (node (ref "R12") (pin "1") (pinfunction "1_1") (pintype "passive"))
      (node (ref "S2") (pin "4") (pinfunction "4_4") (pintype "bidirectional"))
    )
    (net (code "53") (name "A25") (class "Default")
      (node (ref "IC2") (pin "55") (pinfunction "A25_55") (pintype "bidirectional"))
      (node (ref "R13") (pin "1") (pinfunction "1_1") (pintype "passive"))
      (node (ref "S2") (pin "8") (pinfunction "8_8") (pintype "bidirectional"))
    )
    (net (code "54") (name "DQ0") (class "Default")
      (node (ref "CONN1") (pin "31") (pinfunction "31_31") (pintype "bidirectional"))
      (node (ref "CONN2") (pin "14") (pinfunction "14_14") (pintype "passive"))
      (node (ref "IC2") (pin "35") (pinfunction "DQ0_35") (pintype "bidirectional"))
      (node (ref "IC4") (pin "2") (pinfunction "GPIO0_2") (pintype "bidirectional"))
    )
    (net (code "55") (name "DQ1") (class "Default")
      (node (ref "CONN1") (pin "30") (pinfunction "30_30") (pintype "bidirectional"))
      (node (ref "CONN2") (pin "12") (pinfunction "12_12") (pintype "passive"))
      (node (ref "IC2") (pin "37") (pinfunction "DQ1_37") (pintype "bidirectional"))
      (node (ref "IC4") (pin "3") (pinfunction "GPIO1_3") (pintype "bidirectional"))
    )
    (net (code "56") (name "DQ2") (class "Default")
      (node (ref "CONN1") (pin "29") (pinfunction "29_29") (pintype "bidirectional"))
      (node (ref "CONN2") (pin "10") (pinfunction "10_10") (pintype "passive"))
      (node (ref "IC2") (pin "39") (pinfunction "DQ2_39") (pintype "bidirectional"))
      (node (ref "IC4") (pin "4") (pinfunction "GPIO2_4") (pintype "bidirectional"))
    )
    (net (code "57") (name "DQ3") (class "Default")
      (node (ref "CONN1") (pin "4") (pinfunction "4_4") (pintype "bidirectional"))
      (node (ref "CONN2") (pin "7") (pinfunction "7_7") (pintype "passive"))
      (node (ref "IC2") (pin "41") (pinfunction "DQ3_41") (pintype "bidirectional"))
      (node (ref "IC4") (pin "5") (pinfunction "GPIO3_5") (pintype "bidirectional"))
    )
    (net (code "58") (name "DQ4") (class "Default")
      (node (ref "CONN1") (pin "5") (pinfunction "5_5") (pintype "bidirectional"))
      (node (ref "CONN2") (pin "9") (pinfunction "9_9") (pintype "passive"))
      (node (ref "IC2") (pin "44") (pinfunction "DQ4_44") (pintype "bidirectional"))
      (node (ref "IC4") (pin "6") (pinfunction "GPIO4_6") (pintype "bidirectional"))
    )
    (net (code "59") (name "DQ5") (class "Default")
      (node (ref "CONN1") (pin "6") (pinfunction "6_6") (pintype "bidirectional"))
      (node (ref "CONN2") (pin "11") (pinfunction "11_11") (pintype "passive"))
      (node (ref "IC2") (pin "46") (pinfunction "DQ5_46") (pintype "bidirectional"))
      (node (ref "IC4") (pin "7") (pinfunction "GPIO5_7") (pintype "bidirectional"))
    )
    (net (code "60") (name "DQ6") (class "Default")
      (node (ref "CONN1") (pin "7") (pinfunction "7_7") (pintype "bidirectional"))
      (node (ref "CONN2") (pin "13") (pinfunction "13_13") (pintype "passive"))
      (node (ref "IC2") (pin "48") (pinfunction "DQ6_48") (pintype "bidirectional"))
      (node (ref "IC4") (pin "8") (pinfunction "GPIO6_8") (pintype "bidirectional"))
    )
    (net (code "61") (name "DQ7") (class "Default")
      (node (ref "CONN1") (pin "32") (pinfunction "32_32") (pintype "bidirectional"))
      (node (ref "CONN2") (pin "16") (pinfunction "16_16") (pintype "passive"))
      (node (ref "IC2") (pin "50") (pinfunction "DQ7_50") (pintype "bidirectional"))
      (node (ref "IC4") (pin "9") (pinfunction "GPIO7_9") (pintype "bidirectional"))
    )
    (net (code "62") (name "DQ8") (class "Default")
      (node (ref "CONN1") (pin "35") (pinfunction "35_35") (pintype "bidirectional"))
      (node (ref "CONN2") (pin "22") (pinfunction "22_22") (pintype "passive"))
      (node (ref "IC2") (pin "36") (pinfunction "DQ8_36") (pintype "bidirectional"))
      (node (ref "IC4") (pin "11") (pinfunction "GPIO8_11") (pintype "bidirectional"))
    )
    (net (code "63") (name "DQ9") (class "Default")
      (node (ref "CONN1") (pin "34") (pinfunction "34_34") (pintype "bidirectional"))
      (node (ref "CONN2") (pin "20") (pinfunction "20_20") (pintype "passive"))
      (node (ref "IC2") (pin "38") (pinfunction "DQ9_38") (pintype "bidirectional"))
      (node (ref "IC4") (pin "12") (pinfunction "GPIO9_12") (pintype "bidirectional"))
    )
    (net (code "64") (name "DQ10") (class "Default")
      (node (ref "CONN1") (pin "33") (pinfunction "33_33") (pintype "bidirectional"))
      (node (ref "CONN2") (pin "18") (pinfunction "18_18") (pintype "passive"))
      (node (ref "IC2") (pin "40") (pinfunction "DQ10_40") (pintype "bidirectional"))
      (node (ref "IC4") (pin "13") (pinfunction "GPIO10_13") (pintype "bidirectional"))
    )
    (net (code "65") (name "DQ11") (class "Default")
      (node (ref "CONN1") (pin "8") (pinfunction "8_8") (pintype "bidirectional"))
      (node (ref "CONN2") (pin "15") (pinfunction "15_15") (pintype "passive"))
      (node (ref "IC2") (pin "42") (pinfunction "DQ11_42") (pintype "bidirectional"))
      (node (ref "IC4") (pin "14") (pinfunction "GPIO11_14") (pintype "bidirectional"))
    )
    (net (code "66") (name "DQ12") (class "Default")
      (node (ref "CONN1") (pin "9") (pinfunction "9_9") (pintype "bidirectional"))
      (node (ref "CONN2") (pin "17") (pinfunction "17_17") (pintype "passive"))
      (node (ref "IC2") (pin "45") (pinfunction "DQ12_45") (pintype "bidirectional"))
      (node (ref "IC4") (pin "15") (pinfunction "GPIO12_15") (pintype "bidirectional"))
    )
    (net (code "67") (name "DQ13") (class "Default")
      (node (ref "CONN1") (pin "10") (pinfunction "10_10") (pintype "bidirectional"))
      (node (ref "CONN2") (pin "19") (pinfunction "19_19") (pintype "passive"))
      (node (ref "IC2") (pin "47") (pinfunction "DQ13_47") (pintype "bidirectional"))
      (node (ref "IC4") (pin "16") (pinfunction "GPIO13_16") (pintype "bidirectional"))
    )
    (net (code "68") (name "DQ14") (class "Default")
      (node (ref "CONN1") (pin "36") (pinfunction "36_36") (pintype "bidirectional"))
      (node (ref "CONN2") (pin "24") (pinfunction "24_24") (pintype "passive"))
      (node (ref "IC2") (pin "49") (pinfunction "DQ14_49") (pintype "bidirectional"))
      (node (ref "IC4") (pin "17") (pinfunction "GPIO14_17") (pintype "bidirectional"))
    )
    (net (code "69") (name "DQ15") (class "Default")
      (node (ref "CONN1") (pin "11") (pinfunction "11_11") (pintype "bidirectional"))
      (node (ref "CONN2") (pin "21") (pinfunction "21_21") (pintype "passive"))
      (node (ref "IC2") (pin "51") (pinfunction "DQ15/A-1_51") (pintype "bidirectional"))
      (node (ref "IC4") (pin "18") (pinfunction "GPIO15_18") (pintype "bidirectional"))
    )
    (net (code "70") (name "EXT_CART") (class "Default")
      (node (ref "CONN1") (pin "24") (pinfunction "24_24") (pintype "bidirectional"))
      (node (ref "R15") (pin "2") (pinfunction "2_2") (pintype "passive"))
    )
    (net (code "71") (name "GND") (class "Default")
      (node (ref "C1") (pin "2") (pinfunction "2_2") (pintype "passive"))
      (node (ref "C10") (pin "1") (pinfunction "1_1") (pintype "passive"))
      (node (ref "C11") (pin "1") (pinfunction "1_1") (pintype "passive"))
      (node (ref "C2") (pin "2") (pinfunction "2_2") (pintype "passive"))
      (node (ref "C27") (pin "2") (pinfunction "2_2") (pintype "passive"))
      (node (ref "C28") (pin "2") (pinfunction "2_2") (pintype "passive"))
      (node (ref "C29") (pin "2") (pinfunction "2_2") (pintype "passive"))
      (node (ref "C3") (pin "2") (pinfunction "2_2") (pintype "passive"))
      (node (ref "C30") (pin "2") (pinfunction "2_2") (pintype "passive"))
      (node (ref "C31") (pin "2") (pinfunction "2_2") (pintype "passive"))
      (node (ref "C32") (pin "2") (pinfunction "2_2") (pintype "passive"))
      (node (ref "C33") (pin "2") (pinfunction "2_2") (pintype "passive"))
      (node (ref "C34") (pin "2") (pinfunction "2_2") (pintype "passive"))
      (node (ref "C35") (pin "2") (pinfunction "2_2") (pintype "passive"))
      (node (ref "C36") (pin "2") (pinfunction "2_2") (pintype "passive"))
      (node (ref "C37") (pin "2") (pinfunction "2_2") (pintype "passive"))
      (node (ref "C38") (pin "2") (pinfunction "2_2") (pintype "passive"))
      (node (ref "C39") (pin "2") (pinfunction "2_2") (pintype "passive"))
      (node (ref "C4") (pin "2") (pinfunction "2_2") (pintype "passive"))
      (node (ref "C40") (pin "2") (pinfunction "2_2") (pintype "passive"))
      (node (ref "C41") (pin "2") (pinfunction "2_2") (pintype "passive"))
      (node (ref "C42") (pin "1") (pinfunction "1_1") (pintype "passive"))
      (node (ref "C43") (pin "1") (pinfunction "1_1") (pintype "passive"))
      (node (ref "C5") (pin "1") (pinfunction "1_1") (pintype "passive"))
      (node (ref "C6") (pin "2") (pinfunction "2_2") (pintype "passive"))
      (node (ref "C7") (pin "2") (pinfunction "2_2") (pintype "passive"))
      (node (ref "C8") (pin "2") (pinfunction "2_2") (pintype "passive"))
      (node (ref "C9") (pin "2") (pinfunction "2_2") (pintype "passive"))
      (node (ref "CONN1") (pin "2") (pinfunction "2_2") (pintype "bidirectional"))
      (node (ref "CONN1") (pin "23") (pinfunction "23_23") (pintype "bidirectional"))
      (node (ref "CONN1") (pin "3") (pinfunction "3_3") (pintype "bidirectional"))
      (node (ref "CONN2") (pin "3") (pinfunction "3_3") (pintype "passive"))
      (node (ref "CONN2") (pin "47") (pinfunction "47_47") (pintype "passive"))
      (node (ref "CONN2") (pin "5") (pinfunction "5_5") (pintype "passive"))
      (node (ref "IC1") (pin "2") (pinfunction "1A_2") (pintype "bidirectional"))
      (node (ref "IC1") (pin "7") (pinfunction "GND_7") (pintype "bidirectional"))
      (node (ref "IC2") (pin "33") (pinfunction "VSS_1_33") (pintype "bidirectional"))
      (node (ref "IC2") (pin "52") (pinfunction "VSS_2_52") (pintype "bidirectional"))
      (node (ref "IC4") (pin "19") (pinfunction "TESTEN_19") (pintype "passive"))
      (node (ref "IC4") (pin "57") (pinfunction "GND_57") (pintype "power_in"))
      (node (ref "IC4") (pin "58") (pinfunction "GND_58") (pintype "power_in"))
      (node (ref "IC4") (pin "59") (pinfunction "GND_59") (pintype "power_in"))
      (node (ref "IC4") (pin "60") (pinfunction "GND_60") (pintype "power_in"))
      (node (ref "IC4") (pin "61") (pinfunction "GND_61") (pintype "power_in"))
      (node (ref "IC4") (pin "62") (pinfunction "GND_62") (pintype "power_in"))
      (node (ref "IC4") (pin "63") (pinfunction "GND_63") (pintype "power_in"))
      (node (ref "IC4") (pin "64") (pinfunction "GND_64") (pintype "power_in"))
      (node (ref "IC4") (pin "65") (pinfunction "GND_65") (pintype "power_in"))
      (node (ref "IC4") (pin "66") (pinfunction "GND_66") (pintype "power_in"))
      (node (ref "IC6") (pin "10") (pinfunction "GND_10") (pintype "bidirectional"))
      (node (ref "IC7") (pin "10") (pinfunction "GND_10") (pintype "bidirectional"))
      (node (ref "J1") (pin "5") (pinfunction "5_5") (pintype "passive"))
      (node (ref "J1") (pin "S1") (pinfunction "SHIELD_S1") (pintype "passive"))
      (node (ref "J1") (pin "S2") (pinfunction "SHIELD_S2") (pintype "passive"))
      (node (ref "J1") (pin "S3") (pinfunction "SHIELD_S3") (pintype "passive"))
      (node (ref "J1") (pin "S4") (pinfunction "SHIELD_S4") (pintype "passive"))
      (node (ref "J1") (pin "S5") (pinfunction "SHIELD_S5") (pintype "passive"))
      (node (ref "J1") (pin "S6") (pinfunction "SHIELD_S6") (pintype "passive"))
      (node (ref "R17") (pin "1") (pinfunction "1_1") (pintype "passive"))
      (node (ref "S2") (pin "C1") (pinfunction "C1_C1") (pintype "bidirectional"))
      (node (ref "S2") (pin "C2") (pinfunction "C2_C2") (pintype "bidirectional"))
      (node (ref "S4") (pin "3") (pinfunction "P_3") (pintype "passive"))
      (node (ref "S4") (pin "4") (pinfunction "P1_4") (pintype "passive"))
      (node (ref "SW1") (pin "7") (pinfunction "6_7") (pintype "passive"))
      (node (ref "U3") (pin "1") (pinfunction "GND_1") (pintype "input"))
      (node (ref "U4") (pin "4") (pinfunction "GND_4") (pintype "power_in"))
      (node (ref "Y2") (pin "2") (pinfunction "GND_2") (pintype "power_in"))
      (node (ref "Y2") (pin "4") (pinfunction "GND_4") (pintype "power_in"))
    )
    (net (code "72") (name "Net-(S4-S)") (class "Default")
      (node (ref "R19") (pin "1") (pinfunction "1_1") (pintype "passive"))
      (node (ref "S4") (pin "1") (pinfunction "S_1") (pintype "passive"))
      (node (ref "S4") (pin "2") (pinfunction "S1_2") (pintype "passive"))
    )
    (net (code "73") (name "Net-(Y2-2)") (class "Default")
      (node (ref "C43") (pin "2") (pinfunction "2_2") (pintype "passive"))
      (node (ref "R22") (pin "1") (pinfunction "1_1") (pintype "passive"))
      (node (ref "Y2") (pin "3") (pinfunction "2_3") (pintype "passive"))
    )
    (net (code "74") (name "OE1") (class "Default")
      (node (ref "IC4") (pin "40") (pinfunction "GPIO28_ADC2_40") (pintype "bidirectional"))
      (node (ref "IC6") (pin "11") (pinfunction "LE_11") (pintype "bidirectional"))
    )
    (net (code "75") (name "OE2") (class "Default")
      (node (ref "IC4") (pin "41") (pinfunction "GPIO29_ADC3_41") (pintype "bidirectional"))
      (node (ref "IC7") (pin "11") (pinfunction "LE_11") (pintype "bidirectional"))
    )
    (net (code "76") (name "QSPI_SCLK") (class "Default")
      (node (ref "IC4") (pin "52") (pinfunction "QSPI_SCLK_52") (pintype "output"))
      (node (ref "U4") (pin "6") (pinfunction "CLK_6") (pintype "input"))
    )
    (net (code "77") (name "QSPI_SD0") (class "Default")
      (node (ref "IC4") (pin "53") (pinfunction "QSPI_SD0_53") (pintype "bidirectional"))
      (node (ref "U4") (pin "5") (pinfunction "DI(IO0)_5") (pintype "bidirectional"))
    )
    (net (code "78") (name "QSPI_SD1") (class "Default")
      (node (ref "IC4") (pin "55") (pinfunction "QSPI_SD1_55") (pintype "bidirectional"))
      (node (ref "U4") (pin "2") (pinfunction "DO(IO1)_2") (pintype "bidirectional"))
    )
    (net (code "79") (name "QSPI_SD2") (class "Default")
      (node (ref "IC4") (pin "54") (pinfunction "QSPI_SD2_54") (pintype "bidirectional"))
      (node (ref "U4") (pin "3") (pinfunction "~{WP}(IO2)_3") (pintype "bidirectional"))
    )
    (net (code "80") (name "QSPI_SD3") (class "Default")
      (node (ref "IC4") (pin "51") (pinfunction "QSPI_SD3_51") (pintype "bidirectional"))
      (node (ref "U4") (pin "7") (pinfunction "~{HOLD}/~{RESET}/IO3_7") (pintype "bidirectional"))
    )
    (net (code "81") (name "QSPI_SS") (class "Default")
      (node (ref "IC4") (pin "56") (pinfunction "QSPI_SS_56") (pintype "bidirectional"))
      (node (ref "R19") (pin "2") (pinfunction "2_2") (pintype "passive"))
      (node (ref "U4") (pin "1") (pinfunction "~{CS}_1") (pintype "input"))
    )
    (net (code "82") (name "RAM_CSB") (class "Default")
      (node (ref "CONN1") (pin "26") (pinfunction "26_26") (pintype "bidirectional"))
      (node (ref "CONN2") (pin "4") (pinfunction "4_4") (pintype "passive"))
      (node (ref "IC1") (pin "9") (pinfunction "3A_9") (pintype "bidirectional"))
      (node (ref "IC4") (pin "27") (pinfunction "GPIO16_27") (pintype "bidirectional"))
    )
    (net (code "83") (name "RAM_RWB") (class "Default")
      (node (ref "CONN1") (pin "1") (pinfunction "1_1") (pintype "bidirectional"))
      (node (ref "CONN2") (pin "1") (pinfunction "1_1") (pintype "passive"))
      (node (ref "IC1") (pin "5") (pinfunction "2A_5") (pintype "bidirectional"))
      (node (ref "IC4") (pin "28") (pinfunction "GPIO17_28") (pintype "bidirectional"))
    )
    (net (code "84") (name "ROM0_1") (class "Default")
      (node (ref "CONN1") (pin "48") (pinfunction "48_48") (pintype "bidirectional"))
      (node (ref "CONN2") (pin "50") (pinfunction "50_50") (pintype "passive"))
      (node (ref "IC1") (pin "12") (pinfunction "4A_12") (pintype "bidirectional"))
      (node (ref "IC4") (pin "29") (pinfunction "GPIO18_29") (pintype "bidirectional"))
    )
    (net (code "85") (name "ROM_CSB2") (class "Default")
      (node (ref "CONN1") (pin "28") (pinfunction "28_28") (pintype "bidirectional"))
      (node (ref "CONN2") (pin "8") (pinfunction "8_8") (pintype "passive"))
      (node (ref "IC4") (pin "30") (pinfunction "GPIO19_30") (pintype "bidirectional"))
    )
    (net (code "86") (name "SENSE") (class "Default")
      (node (ref "CONN1") (pin "27") (pinfunction "27_27") (pintype "bidirectional"))
      (node (ref "R16") (pin "2") (pinfunction "2_2") (pintype "passive"))
    )
    (net (code "87") (name "USB1_N") (class "Default")
      (node (ref "IC4") (pin "46") (pinfunction "USB_DM_46") (pintype "bidirectional"))
      (node (ref "R21") (pin "1") (pinfunction "1_1") (pintype "passive"))
    )
    (net (code "88") (name "USB1_P") (class "Default")
      (node (ref "IC4") (pin "47") (pinfunction "USB_DP_47") (pintype "bidirectional"))
      (node (ref "R20") (pin "1") (pinfunction "1_1") (pintype "passive"))
    )
    (net (code "89") (name "USB_N") (class "Default")
      (node (ref "J1") (pin "2") (pinfunction "2_2") (pintype "passive"))
      (node (ref "R21") (pin "2") (pinfunction "2_2") (pintype "passive"))
    )
    (net (code "90") (name "USB_P") (class "Default")
      (node (ref "J1") (pin "3") (pinfunction "3_3") (pintype "passive"))
      (node (ref "R20") (pin "2") (pinfunction "2_2") (pintype "passive"))
    )
    (net (code "91") (name "VBUS") (class "Default")
      (node (ref "C38") (pin "1") (pinfunction "1_1") (pintype "passive"))
      (node (ref "J1") (pin "1") (pinfunction "1_1") (pintype "passive"))
      (node (ref "U3") (pin "3") (pinfunction "IN_3") (pintype "input"))
    )
    (net (code "92") (name "VCC") (class "Default")
      (node (ref "C1") (pin "1") (pinfunction "1_1") (pintype "passive"))
      (node (ref "C2") (pin "1") (pinfunction "1_1") (pintype "passive"))
      (node (ref "C4") (pin "1") (pinfunction "1_1") (pintype "passive"))
      (node (ref "D1") (pin "3") (pinfunction "C_3") (pintype "passive"))
      (node (ref "IC1") (pin "14") (pinfunction "VCC_14") (pintype "bidirectional"))
      (node (ref "IC2") (pin "29") (pinfunction "VCCQ_29") (pintype "bidirectional"))
      (node (ref "IC2") (pin "43") (pinfunction "VCC_43") (pintype "bidirectional"))
      (node (ref "R1") (pin "2") (pinfunction "2_2") (pintype "passive"))
      (node (ref "R10") (pin "2") (pinfunction "2_2") (pintype "passive"))
      (node (ref "R11") (pin "2") (pinfunction "2_2") (pintype "passive"))
      (node (ref "R12") (pin "2") (pinfunction "2_2") (pintype "passive"))
      (node (ref "R13") (pin "2") (pinfunction "2_2") (pintype "passive"))
      (node (ref "R14") (pin "2") (pinfunction "2_2") (pintype "passive"))
      (node (ref "R2") (pin "2") (pinfunction "2_2") (pintype "passive"))
      (node (ref "R3") (pin "2") (pinfunction "2_2") (pintype "passive"))
      (node (ref "R4") (pin "2") (pinfunction "2_2") (pintype "passive"))
      (node (ref "R5") (pin "2") (pinfunction "2_2") (pintype "passive"))
      (node (ref "R6") (pin "2") (pinfunction "2_2") (pintype "passive"))
      (node (ref "R7") (pin "2") (pinfunction "2_2") (pintype "passive"))
      (node (ref "R8") (pin "2") (pinfunction "2_2") (pintype "passive"))
      (node (ref "R9") (pin "2") (pinfunction "2_2") (pintype "passive"))
    )
    (net (code "93") (name "VDD_EXT") (class "Default")
      (node (ref "CONN1") (pin "25") (pinfunction "25_25") (pintype "bidirectional"))
      (node (ref "D1") (pin "2") (pinfunction "A2_2") (pintype "passive"))
      (node (ref "R15") (pin "1") (pinfunction "1_1") (pintype "passive"))
      (node (ref "R16") (pin "1") (pinfunction "1_1") (pintype "passive"))
    )
    (net (code "94") (name "XIN") (class "Default")
      (node (ref "C42") (pin "2") (pinfunction "2_2") (pintype "passive"))
      (node (ref "IC4") (pin "20") (pinfunction "XIN_20") (pintype "input"))
      (node (ref "Y2") (pin "1") (pinfunction "1_1") (pintype "passive"))
    )
    (net (code "95") (name "XOUT") (class "Default")
      (node (ref "IC4") (pin "21") (pinfunction "XOUT_21") (pintype "passive"))
      (node (ref "R22") (pin "2") (pinfunction "2_2") (pintype "passive"))
    )
    (net (code "96") (name "unconnected-(CONN2-Pad6)") (class "Default")
      (node (ref "CONN2") (pin "6") (pinfunction "6_6") (pintype "passive"))
    )
    (net (code "97") (name "unconnected-(CONN2-Pad29)") (class "Default")
      (node (ref "CONN2") (pin "29") (pinfunction "29_29") (pintype "passive"))
    )
    (net (code "98") (name "unconnected-(CONN2-Pad30)") (class "Default")
      (node (ref "CONN2") (pin "30") (pinfunction "30_30") (pintype "passive"))
    )
    (net (code "99") (name "unconnected-(CONN2-Pad49)") (class "Default")
      (node (ref "CONN2") (pin "49") (pinfunction "49_49") (pintype "passive"))
    )
    (net (code "100") (name "unconnected-(IC2-RFU_1-Pad27)") (class "Default")
      (node (ref "IC2") (pin "27") (pinfunction "RFU_1_27") (pintype "bidirectional"))
    )
    (net (code "101") (name "unconnected-(IC2-RFU_2-Pad28)") (class "Default")
      (node (ref "IC2") (pin "28") (pinfunction "RFU_2_28") (pintype "bidirectional"))
    )
    (net (code "102") (name "unconnected-(IC2-RFU_3-Pad30)") (class "Default")
      (node (ref "IC2") (pin "30") (pinfunction "RFU_3_30") (pintype "bidirectional"))
    )
    (net (code "103") (name "unconnected-(IC2-RY{slash}BY#-Pad17)") (class "Default")
      (node (ref "IC2") (pin "17") (pinfunction "RY/BY#_17") (pintype "bidirectional"))
    )
    (net (code "104") (name "unconnected-(IC4-RUN-Pad26)") (class "Default")
      (node (ref "IC4") (pin "26") (pinfunction "RUN_26") (pintype "input"))
    )
    (net (code "105") (name "unconnected-(IC4-SWCLK-Pad24)") (class "Default")
      (node (ref "IC4") (pin "24") (pinfunction "SWCLK_24") (pintype "output"))
    )
    (net (code "106") (name "unconnected-(IC4-SWD-Pad25)") (class "Default")
      (node (ref "IC4") (pin "25") (pinfunction "SWD_25") (pintype "bidirectional"))
    )
    (net (code "107") (name "unconnected-(IC7-7Q-Pad16)") (class "Default")
      (node (ref "IC7") (pin "16") (pinfunction "7Q_16") (pintype "bidirectional"))
    )
    (net (code "108") (name "unconnected-(IC7-8Q-Pad19)") (class "Default")
      (node (ref "IC7") (pin "19") (pinfunction "8Q_19") (pintype "bidirectional"))
    )
    (net (code "109") (name "unconnected-(J1-Pad4)") (class "Default")
      (node (ref "J1") (pin "4") (pinfunction "4_4") (pintype "passive"))
    )
    (net (code "110") (name "unconnected-(SW1-5-Pad8)") (class "Default")
      (node (ref "SW1") (pin "8") (pinfunction "5_8") (pintype "passive"))
    )
    (net (code "111") (name "~{BYTE}") (class "Default")
      (node (ref "IC2") (pin "53") (pinfunction "BYTE#_53") (pintype "bidirectional"))
      (node (ref "R14") (pin "1") (pinfunction "1_1") (pintype "passive"))
    )
    (net (code "112") (name "~{CE}") (class "Default")
      (node (ref "IC1") (pin "11") (pinfunction "4B_11") (pintype "bidirectional"))
      (node (ref "IC2") (pin "32") (pinfunction "CE#_32") (pintype "bidirectional"))
      (node (ref "R7") (pin "1") (pinfunction "1_1") (pintype "passive"))
    )
    (net (code "113") (name "~{LATCH_OE}") (class "Default")
      (node (ref "IC6") (pin "1") (pinfunction "~{OE}_1") (pintype "bidirectional"))
      (node (ref "IC7") (pin "1") (pinfunction "~{OE}_1") (pintype "bidirectional"))
      (node (ref "R17") (pin "2") (pinfunction "2_2") (pintype "passive"))
      (node (ref "SW1") (pin "1") (pinfunction "1_1") (pintype "passive"))
    )
    (net (code "114") (name "~{OE}") (class "Default")
      (node (ref "C5") (pin "2") (pinfunction "2_2") (pintype "passive"))
      (node (ref "IC1") (pin "3") (pinfunction "1B_3") (pintype "bidirectional"))
      (node (ref "IC1") (pin "8") (pinfunction "3B_8") (pintype "bidirectional"))
      (node (ref "IC2") (pin "34") (pinfunction "OE#_34") (pintype "bidirectional"))
      (node (ref "R6") (pin "1") (pinfunction "1_1") (pintype "passive"))
    )
    (net (code "115") (name "~{RST}") (class "Default")
      (node (ref "C10") (pin "2") (pinfunction "2_2") (pintype "passive"))
      (node (ref "IC2") (pin "14") (pinfunction "RST#_14") (pintype "bidirectional"))
      (node (ref "R8") (pin "1") (pinfunction "1_1") (pintype "passive"))
    )
    (net (code "116") (name "~{WE}") (class "Default")
      (node (ref "IC1") (pin "6") (pinfunction "2B_6") (pintype "bidirectional"))
      (node (ref "IC2") (pin "13") (pinfunction "WE#_13") (pintype "bidirectional"))
      (node (ref "R5") (pin "1") (pinfunction "1_1") (pintype "passive"))
    )
    (net (code "117") (name "~{WP}") (class "Default")
      (node (ref "C11") (pin "2") (pinfunction "2_2") (pintype "passive"))
      (node (ref "IC2") (pin "16") (pinfunction "V_PP/WP#_16") (pintype "bidirectional"))
      (node (ref "R9") (pin "1") (pinfunction "1_1") (pintype "passive"))
    )
  )
)
